# Sheet1.net
KiCad netlist of a schematic drawn in Altium Designer
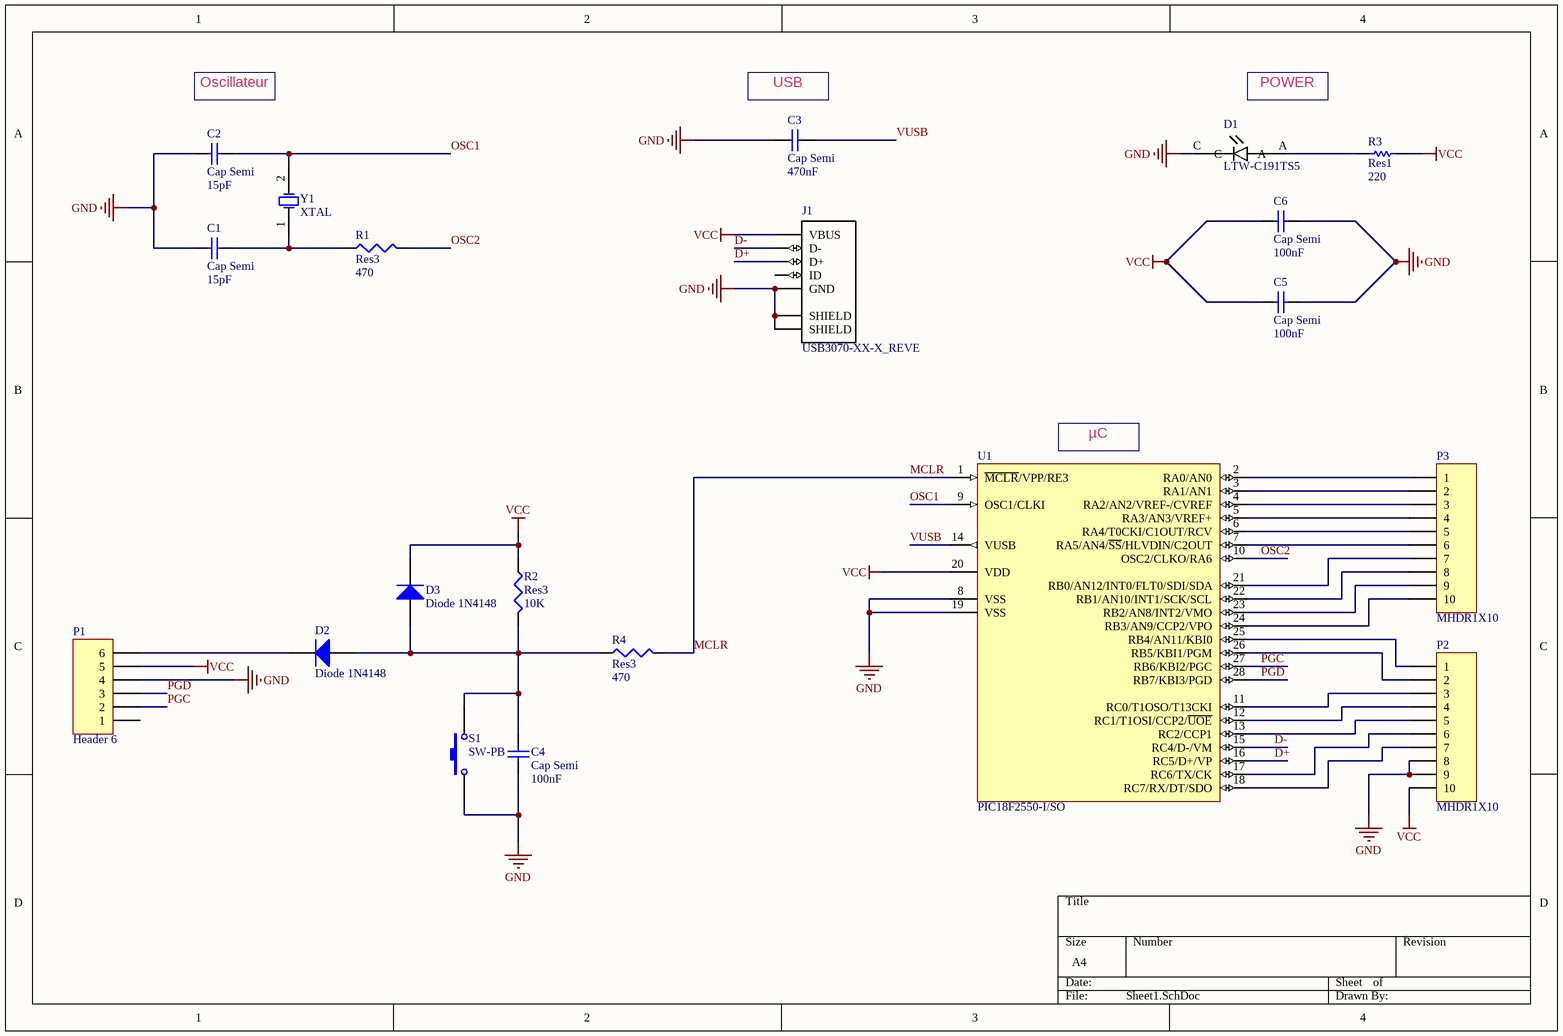
[diagram p0: Sheet1.SchDoc]

(export (version "E")
  (design (tool "Eeschema 10.0.6"))
  (components
    (comp (ref "C1")
      (value "Cap Semi")
      (footprint "C1206")
      (description "Capacitor (Semiconductor SIM Model)")
      (fields (field (name "ALTIUM_VALUE") "15pF") (field (name "PUBLISHER") "Altium Limited"))
      (libsource (lib "Miscellaneous Devices") (part "Cap Semi"))
    )
    (comp (ref "C2")
      (value "Cap Semi")
      (footprint "C1206")
      (description "Capacitor (Semiconductor SIM Model)")
      (fields (field (name "ALTIUM_VALUE") "15pF") (field (name "PUBLISHER") "Altium Limited"))
      (libsource (lib "Miscellaneous Devices") (part "Cap Semi"))
    )
    (comp (ref "C3")
      (value "Cap Semi")
      (footprint "C1206")
      (description "Capacitor (Semiconductor SIM Model)")
      (fields (field (name "ALTIUM_VALUE") "470nF") (field (name "PUBLISHER") "Altium Limited"))
      (libsource (lib "Miscellaneous Devices") (part "Cap Semi"))
    )
    (comp (ref "C4")
      (value "Cap Semi")
      (footprint "C1206")
      (description "Capacitor (Semiconductor SIM Model)")
      (fields (field (name "ALTIUM_VALUE") "100nF") (field (name "PUBLISHER") "Altium Limited"))
      (libsource (lib "Miscellaneous Devices") (part "Cap Semi"))
    )
    (comp (ref "C5")
      (value "Cap Semi")
      (footprint "C1206")
      (description "Capacitor (Semiconductor SIM Model)")
      (fields (field (name "ALTIUM_VALUE") "100nF") (field (name "PUBLISHER") "Altium Limited"))
      (libsource (lib "Miscellaneous Devices") (part "Cap Semi"))
    )
    (comp (ref "C6")
      (value "Cap Semi")
      (footprint "C1206")
      (description "Capacitor (Semiconductor SIM Model)")
      (fields (field (name "ALTIUM_VALUE") "100nF") (field (name "PUBLISHER") "Altium Limited"))
      (libsource (lib "Miscellaneous Devices") (part "Cap Semi"))
    )
    (comp (ref "D1")
      (value "LTW-C191TS5")
      (footprint "LEDM1608X55_LTW-C191TS5(Primary)")
      (description "Yellow 1.6 x 0.8 x 0.55 mm 130%C2%B0 Tinted/Diffused 180 mcd 3.15V LED Surface Mount")
      (fields (field (name "MF") "Lite-On"))
      (libsource (lib "LTW-C191TS5") (part "LTW-C191TS5"))
    )
    (comp (ref "D2")
      (value "Diode 1N4148")
      (footprint "DO-35")
      (description "High Conductance Fast Diode")
      (fields (field (name "PUBLISHER") "Altium Limited"))
      (libsource (lib "Miscellaneous Devices") (part "Diode 1N4148"))
    )
    (comp (ref "D3")
      (value "Diode 1N4148")
      (footprint "DO-35")
      (description "High Conductance Fast Diode")
      (fields (field (name "PUBLISHER") "Altium Limited"))
      (libsource (lib "Miscellaneous Devices") (part "Diode 1N4148"))
    )
    (comp (ref "J1")
      (value "USB3070-XX-X_REVE")
      (footprint "GCT_USB3070-XX-X_REVE")
      (description "5 Position Surface Mount Right Angle Micro USB 2.0 Connector")
      (fields (field (name "MP") "USB3070-30-A") (field (name "MF") "Global Connector Technology"))
      (libsource (lib "USB3070-XX-X_REVE") (part "USB3070-XX-X_REVE"))
    )
    (comp (ref "P1")
      (value "Header 6")
      (footprint "HDR1X6")
      (description "Header, 6-Pin")
      (fields (field (name "PUBLISHER") "Altium Limited"))
      (libsource (lib "Miscellaneous Connectors") (part "Header 6"))
    )
    (comp (ref "P2")
      (value "MHDR1X10")
      (footprint "MHDR1X10")
      (description "Header, 10-Pin")
      (fields (field (name "PUBLISHER") "Altium Limited"))
      (libsource (lib "Miscellaneous Connectors") (part "MHDR1X10"))
    )
    (comp (ref "P3")
      (value "MHDR1X10")
      (footprint "MHDR1X10")
      (description "Header, 10-Pin")
      (fields (field (name "PUBLISHER") "Altium Limited"))
      (libsource (lib "Miscellaneous Connectors") (part "MHDR1X10"))
    )
    (comp (ref "R1")
      (value "Res3")
      (footprint "J1-0603")
      (description "Resistor")
      (fields (field (name "ALTIUM_VALUE") "470") (field (name "PUBLISHER") "Altium Limited"))
      (libsource (lib "Miscellaneous Devices") (part "Res3"))
    )
    (comp (ref "R2")
      (value "Res3")
      (footprint "J1-0603")
      (description "Resistor")
      (fields (field (name "ALTIUM_VALUE") "10K") (field (name "PUBLISHER") "Altium Limited"))
      (libsource (lib "Miscellaneous Devices") (part "Res3"))
    )
    (comp (ref "R3")
      (value "Res1")
      (footprint "AXIAL-0.3")
      (description "Resistor")
      (fields (field (name "ALTIUM_VALUE") "220") (field (name "PUBLISHER") "Altium Limited"))
      (libsource (lib "Miscellaneous Devices") (part "Res1"))
    )
    (comp (ref "R4")
      (value "Res3")
      (footprint "J1-0603")
      (description "Resistor")
      (fields (field (name "ALTIUM_VALUE") "470") (field (name "PUBLISHER") "Altium Limited"))
      (libsource (lib "Miscellaneous Devices") (part "Res3"))
    )
    (comp (ref "S1")
      (value "SW-PB")
      (footprint "SPST-2")
      (description "Switch")
      (fields (field (name "PUBLISHER") "Altium Limited"))
      (libsource (lib "Miscellaneous Devices") (part "SW-PB"))
    )
    (comp (ref "U1")
      (value "PIC18F2550-I/SO")
      (footprint "SOIC-SO28_N")
      (fields (field (name "PUBLISHER") "Altium Limited"))
      (libsource (lib "Microchip Microcontroller 8-Bit PIC18") (part "PIC18F2550-I/SO"))
    )
    (comp (ref "Y1")
      (value "XTAL")
      (footprint "R38")
      (description "Crystal Oscillator")
      (fields (field (name "PUBLISHER") "Altium Limited"))
      (libsource (lib "Miscellaneous Devices") (part "XTAL"))
    )
  )
  (nets
    (net (code "1") (name "/D+") (class "Default")
      (node (ref "J1") (pin "3") (pinfunction "D+_3") (pintype "bidirectional"))
      (node (ref "U1") (pin "16") (pinfunction "RC5/D+/VP_16") (pintype "bidirectional"))
    )
    (net (code "2") (name "/D-") (class "Default")
      (node (ref "J1") (pin "2") (pinfunction "D-_2") (pintype "bidirectional"))
      (node (ref "U1") (pin "15") (pinfunction "RC4/D-/VM_15") (pintype "bidirectional"))
    )
    (net (code "3") (name "/MCLR") (class "Default")
      (node (ref "R4") (pin "2") (pinfunction "2_2") (pintype "passive"))
      (node (ref "U1") (pin "1") (pinfunction "~{MCLR}/VPP/RE3_1") (pintype "input"))
    )
    (net (code "4") (name "/OSC1") (class "Default")
      (node (ref "C2") (pin "2") (pinfunction "2_2") (pintype "passive"))
      (node (ref "U1") (pin "9") (pinfunction "OSC1/CLKI_9") (pintype "input"))
      (node (ref "Y1") (pin "2") (pinfunction "OSC2_2") (pintype "passive"))
    )
    (net (code "5") (name "/OSC2") (class "Default")
      (node (ref "R1") (pin "2") (pinfunction "2_2") (pintype "passive"))
      (node (ref "U1") (pin "10") (pinfunction "OSC2/CLKO/RA6_10") (pintype "bidirectional"))
    )
    (net (code "6") (name "/PGC") (class "Default")
      (node (ref "P1") (pin "2") (pinfunction "2_2") (pintype "passive"))
      (node (ref "U1") (pin "27") (pinfunction "RB6/KBI2/PGC_27") (pintype "bidirectional"))
    )
    (net (code "7") (name "/PGD") (class "Default")
      (node (ref "P1") (pin "3") (pinfunction "3_3") (pintype "passive"))
      (node (ref "U1") (pin "28") (pinfunction "RB7/KBI3/PGD_28") (pintype "bidirectional"))
    )
    (net (code "8") (name "/VUSB") (class "Default")
      (node (ref "C3") (pin "2") (pinfunction "2_2") (pintype "passive"))
      (node (ref "U1") (pin "14") (pinfunction "VUSB_14") (pintype "output"))
    )
    (net (code "9") (name "GND") (class "Default")
      (node (ref "C1") (pin "1") (pinfunction "1_1") (pintype "passive"))
      (node (ref "C2") (pin "1") (pinfunction "1_1") (pintype "passive"))
      (node (ref "C3") (pin "1") (pinfunction "1_1") (pintype "passive"))
      (node (ref "C4") (pin "1") (pinfunction "1_1") (pintype "passive"))
      (node (ref "C5") (pin "1") (pinfunction "1_1") (pintype "passive"))
      (node (ref "C6") (pin "1") (pinfunction "1_1") (pintype "passive"))
      (node (ref "D1") (pin "C") (pinfunction "C_C") (pintype "passive"))
      (node (ref "J1") (pin "5") (pinfunction "GND_5") (pintype "power_in"))
      (node (ref "J1") (pin "6") (pinfunction "SHIELD_6") (pintype "power_in"))
      (node (ref "J1") (pin "7") (pinfunction "SHIELD_7") (pintype "power_in"))
      (node (ref "P1") (pin "4") (pinfunction "4_4") (pintype "passive"))
      (node (ref "P2") (pin "8") (pinfunction "8_8") (pintype "passive"))
      (node (ref "P2") (pin "9") (pinfunction "9_9") (pintype "passive"))
      (node (ref "S1") (pin "1") (pinfunction "1_1") (pintype "passive"))
      (node (ref "U1") (pin "19") (pinfunction "VSS_19") (pintype "power_in"))
      (node (ref "U1") (pin "8") (pinfunction "VSS_8") (pintype "power_in"))
    )
    (net (code "10") (name "Net-(D1-PadA)") (class "Default")
      (node (ref "D1") (pin "A") (pinfunction "A_A") (pintype "passive"))
      (node (ref "R3") (pin "2") (pinfunction "2_2") (pintype "passive"))
    )
    (net (code "11") (name "Net-(D2-A)") (class "Default")
      (node (ref "C4") (pin "2") (pinfunction "2_2") (pintype "passive"))
      (node (ref "D2") (pin "1") (pinfunction "A_1") (pintype "passive"))
      (node (ref "D3") (pin "1") (pinfunction "A_1") (pintype "passive"))
      (node (ref "R2") (pin "2") (pinfunction "2_2") (pintype "passive"))
      (node (ref "R4") (pin "1") (pinfunction "1_1") (pintype "passive"))
      (node (ref "S1") (pin "2") (pinfunction "2_2") (pintype "passive"))
    )
    (net (code "12") (name "Net-(D2-K)") (class "Default")
      (node (ref "D2") (pin "2") (pinfunction "K_2") (pintype "passive"))
      (node (ref "P1") (pin "6") (pinfunction "6_6") (pintype "passive"))
    )
    (net (code "13") (name "Net-(U1-RA0{slash}AN0)") (class "Default")
      (node (ref "P3") (pin "1") (pinfunction "1_1") (pintype "passive"))
      (node (ref "U1") (pin "2") (pinfunction "RA0/AN0_2") (pintype "bidirectional"))
    )
    (net (code "14") (name "Net-(U1-RA1{slash}AN1)") (class "Default")
      (node (ref "P3") (pin "2") (pinfunction "2_2") (pintype "passive"))
      (node (ref "U1") (pin "3") (pinfunction "RA1/AN1_3") (pintype "bidirectional"))
    )
    (net (code "15") (name "Net-(U1-RA2{slash}AN2{slash}VREF-{slash}CVREF)") (class "Default")
      (node (ref "P3") (pin "3") (pinfunction "3_3") (pintype "passive"))
      (node (ref "U1") (pin "4") (pinfunction "RA2/AN2/VREF-/CVREF_4") (pintype "bidirectional"))
    )
    (net (code "16") (name "Net-(U1-RA3{slash}AN3{slash}VREF+)") (class "Default")
      (node (ref "P3") (pin "4") (pinfunction "4_4") (pintype "passive"))
      (node (ref "U1") (pin "5") (pinfunction "RA3/AN3/VREF+_5") (pintype "bidirectional"))
    )
    (net (code "17") (name "Net-(U1-RA4{slash}T0CKI{slash}C1OUT{slash}RCV)") (class "Default")
      (node (ref "P3") (pin "5") (pinfunction "5_5") (pintype "passive"))
      (node (ref "U1") (pin "6") (pinfunction "RA4/T0CKI/C1OUT/RCV_6") (pintype "bidirectional"))
    )
    (net (code "18") (name "Net-(U1-RA5{slash}AN4{slash}~{SS}{slash}HLVDIN{slash}C2OUT)") (class "Default")
      (node (ref "P3") (pin "6") (pinfunction "6_6") (pintype "passive"))
      (node (ref "U1") (pin "7") (pinfunction "RA5/AN4/~{SS}/HLVDIN/C2OUT_7") (pintype "bidirectional"))
    )
    (net (code "19") (name "Net-(U1-RB0{slash}AN12{slash}INT0{slash}FLT0{slash}SDI{slash}SDA)") (class "Default")
      (node (ref "P3") (pin "7") (pinfunction "7_7") (pintype "passive"))
      (node (ref "U1") (pin "21") (pinfunction "RB0/AN12/INT0/FLT0/SDI/SDA_21") (pintype "bidirectional"))
    )
    (net (code "20") (name "Net-(U1-RB1{slash}AN10{slash}INT1{slash}SCK{slash}SCL)") (class "Default")
      (node (ref "P3") (pin "8") (pinfunction "8_8") (pintype "passive"))
      (node (ref "U1") (pin "22") (pinfunction "RB1/AN10/INT1/SCK/SCL_22") (pintype "bidirectional"))
    )
    (net (code "21") (name "Net-(U1-RB2{slash}AN8{slash}INT2{slash}VMO)") (class "Default")
      (node (ref "P3") (pin "9") (pinfunction "9_9") (pintype "passive"))
      (node (ref "U1") (pin "23") (pinfunction "RB2/AN8/INT2/VMO_23") (pintype "bidirectional"))
    )
    (net (code "22") (name "Net-(U1-RB3{slash}AN9{slash}CCP2{slash}VPO)") (class "Default")
      (node (ref "P3") (pin "10") (pinfunction "10_10") (pintype "passive"))
      (node (ref "U1") (pin "24") (pinfunction "RB3/AN9/CCP2/VPO_24") (pintype "bidirectional"))
    )
    (net (code "23") (name "Net-(U1-RB4{slash}AN11{slash}KBI0)") (class "Default")
      (node (ref "P2") (pin "1") (pinfunction "1_1") (pintype "passive"))
      (node (ref "U1") (pin "25") (pinfunction "RB4/AN11/KBI0_25") (pintype "bidirectional"))
    )
    (net (code "24") (name "Net-(U1-RB5{slash}KBI1{slash}PGM)") (class "Default")
      (node (ref "P2") (pin "2") (pinfunction "2_2") (pintype "passive"))
      (node (ref "U1") (pin "26") (pinfunction "RB5/KBI1/PGM_26") (pintype "bidirectional"))
    )
    (net (code "25") (name "Net-(U1-RC0{slash}T1OSO{slash}T13CKI)") (class "Default")
      (node (ref "P2") (pin "3") (pinfunction "3_3") (pintype "passive"))
      (node (ref "U1") (pin "11") (pinfunction "RC0/T1OSO/T13CKI_11") (pintype "bidirectional"))
    )
    (net (code "26") (name "Net-(U1-RC1{slash}T1OSI{slash}CCP2{slash}~{UOE})") (class "Default")
      (node (ref "P2") (pin "4") (pinfunction "4_4") (pintype "passive"))
      (node (ref "U1") (pin "12") (pinfunction "RC1/T1OSI/CCP2/~{UOE}_12") (pintype "bidirectional"))
    )
    (net (code "27") (name "Net-(U1-RC2{slash}CCP1)") (class "Default")
      (node (ref "P2") (pin "5") (pinfunction "5_5") (pintype "passive"))
      (node (ref "U1") (pin "13") (pinfunction "RC2/CCP1_13") (pintype "bidirectional"))
    )
    (net (code "28") (name "Net-(U1-RC6{slash}TX{slash}CK)") (class "Default")
      (node (ref "P2") (pin "6") (pinfunction "6_6") (pintype "passive"))
      (node (ref "U1") (pin "17") (pinfunction "RC6/TX/CK_17") (pintype "bidirectional"))
    )
    (net (code "29") (name "Net-(U1-RC7{slash}RX{slash}DT{slash}SDO)") (class "Default")
      (node (ref "P2") (pin "7") (pinfunction "7_7") (pintype "passive"))
      (node (ref "U1") (pin "18") (pinfunction "RC7/RX/DT/SDO_18") (pintype "bidirectional"))
    )
    (net (code "30") (name "Net-(Y1-OSC1)") (class "Default")
      (node (ref "C1") (pin "2") (pinfunction "2_2") (pintype "passive"))
      (node (ref "R1") (pin "1") (pinfunction "1_1") (pintype "passive"))
      (node (ref "Y1") (pin "1") (pinfunction "OSC1_1") (pintype "passive"))
    )
    (net (code "31") (name "VCC") (class "Default")
      (node (ref "C5") (pin "2") (pinfunction "2_2") (pintype "passive"))
      (node (ref "C6") (pin "2") (pinfunction "2_2") (pintype "passive"))
      (node (ref "D3") (pin "2") (pinfunction "K_2") (pintype "passive"))
      (node (ref "J1") (pin "1") (pinfunction "VBUS_1") (pintype "power_in"))
      (node (ref "P1") (pin "5") (pinfunction "5_5") (pintype "passive"))
      (node (ref "P2") (pin "10") (pinfunction "10_10") (pintype "passive"))
      (node (ref "R2") (pin "1") (pinfunction "1_1") (pintype "passive"))
      (node (ref "R3") (pin "1") (pinfunction "1_1") (pintype "passive"))
      (node (ref "U1") (pin "20") (pinfunction "VDD_20") (pintype "power_in"))
    )
    (net (code "32") (name "unconnected-(J1-ID-Pad4)") (class "Default")
      (node (ref "J1") (pin "4") (pinfunction "ID_4") (pintype "bidirectional"))
    )
    (net (code "33") (name "unconnected-(P1-Pad1)") (class "Default")
      (node (ref "P1") (pin "1") (pinfunction "1_1") (pintype "passive"))
    )
  )
)
